# Greinke_Boost_Converter_Electromagnet_Sc.net
KiCad netlist of a schematic drawn in Altium Designer
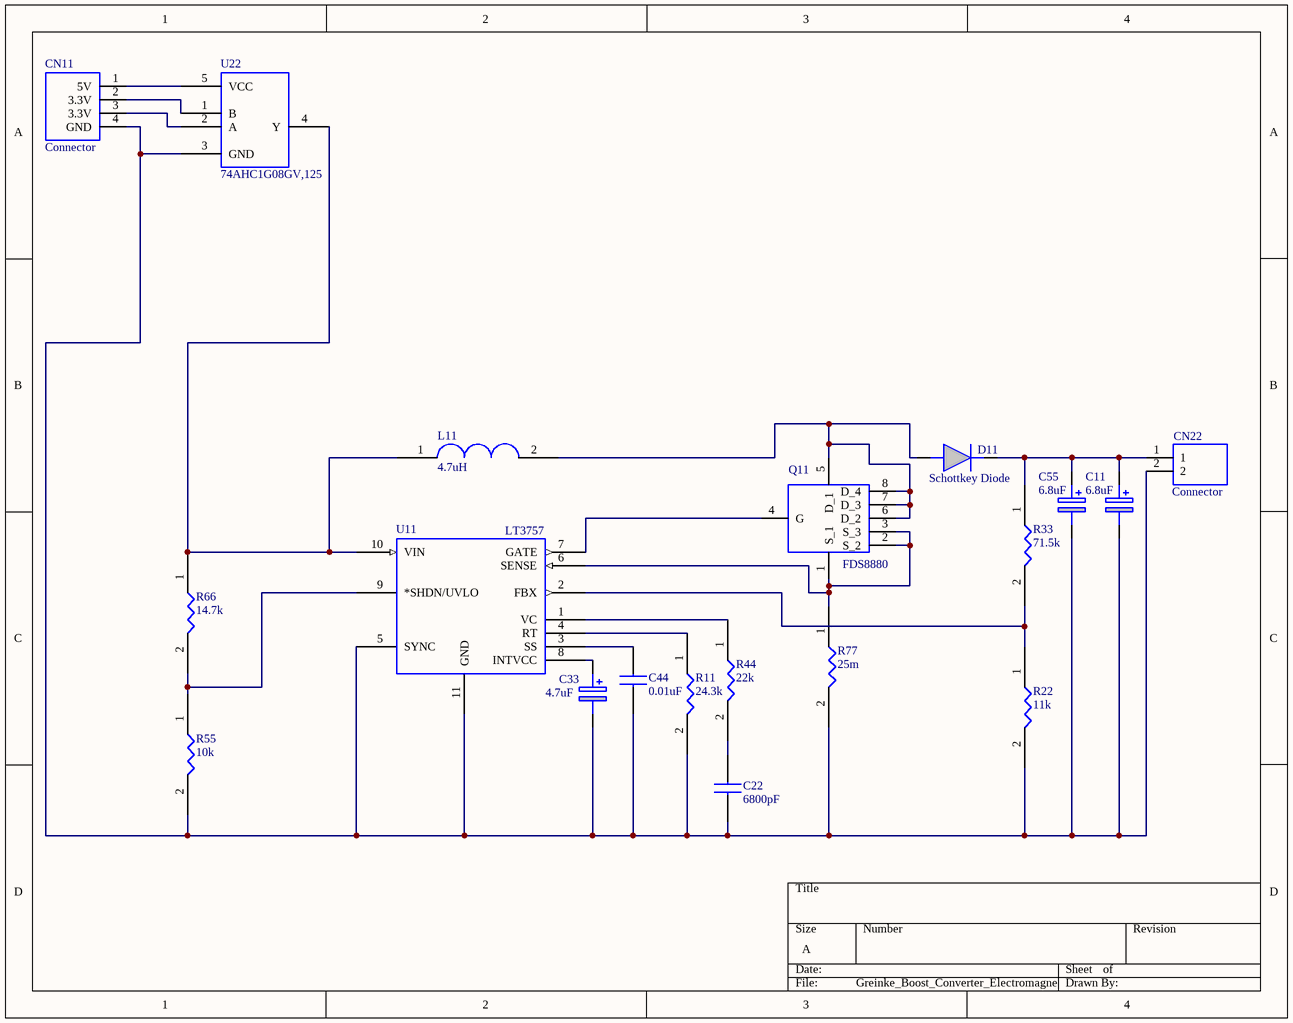
[diagram p0: Greinke_Boost_Converter_Electromagnet(Schematic).SchDoc]

(export (version "E")
  (design (tool "Eeschema 10.0.6"))
  (components
    (comp (ref "C11")
      (value "6.8uF")
      (footprint "6.8u Capacitor")
      (libsource (lib "Schlib1") (part "6.8u Capacitor"))
    )
    (comp (ref "C22")
      (value "6800pF")
      (footprint "6800p Capacitor")
      (libsource (lib "Schlib1") (part "6800p Capacitor"))
    )
    (comp (ref "C33")
      (value "4.7uF")
      (footprint "4.7u Capacitor")
      (libsource (lib "Schlib1") (part "4.7u Capacitor"))
    )
    (comp (ref "C44")
      (value "0.01uF")
      (footprint "0.01u Capacitor")
      (libsource (lib "Schlib1") (part "0.01u Capacitor_1"))
    )
    (comp (ref "C55")
      (value "6.8uF")
      (footprint "6.8u Capacitor")
      (libsource (lib "Schlib1") (part "6.8u Capacitor"))
    )
    (comp (ref "CN11")
      (value "Connector")
      (footprint "4 Terminal Block")
      (libsource (lib "Schlib1") (part "4 Terminal Block"))
    )
    (comp (ref "CN22")
      (value "Connector")
      (footprint "2 Terminal Blocks")
      (libsource (lib "Schlib1") (part "2 Terminal Blocks"))
    )
    (comp (ref "D11")
      (value "Schottkey Diode")
      (footprint "MBRS340")
      (libsource (lib "Schlib1") (part "MBRS340"))
    )
    (comp (ref "L11") (value "4.7uH") (footprint "744774047") (libsource (lib "Schlib1") (part "744774047")))
    (comp (ref "Q11") (value "FDS8880") (footprint "FDS8880") (libsource (lib "Schlib1") (part "FDS8880")))
    (comp (ref "R11")
      (value "24.3k")
      (footprint "24.3k Resistor")
      (libsource (lib "Schlib1") (part "24.3k Resistor"))
    )
    (comp (ref "R22")
      (value "11k")
      (footprint "11k Resistor")
      (libsource (lib "Schlib1") (part "11k Resistor"))
    )
    (comp (ref "R33")
      (value "71.5k")
      (footprint "71.5k Resistor")
      (libsource (lib "Schlib1") (part "71.5k Resistor"))
    )
    (comp (ref "R44")
      (value "22k")
      (footprint "22k Resistor")
      (libsource (lib "Schlib1") (part "22k Resistor"))
    )
    (comp (ref "R55")
      (value "10k")
      (footprint "10k Resistor")
      (libsource (lib "Schlib1") (part "10k Resistor"))
    )
    (comp (ref "R66")
      (value "14.7k")
      (footprint "14.7k Resistor")
      (libsource (lib "Schlib1") (part "14.7k Resistor"))
    )
    (comp (ref "R77")
      (value "25m")
      (footprint "25m Resistor")
      (libsource (lib "Schlib1") (part "25m Resistor"))
    )
    (comp (ref "U11") (value "LT3757") (footprint "LT3757") (libsource (lib "Schlib1") (part "LT3757")))
    (comp (ref "U22")
      (value "74AHC1G08GV,125")
      (footprint "74AHC1G08GV,125")
      (libsource (lib "Schlib1") (part "74AHC1G08GV,125"))
    )
  )
  (nets
    (net (code "1") (name "Net-(C11-+)") (class "Default")
      (node (ref "C11") (pin "1") (pinfunction "+_1") (pintype "passive"))
      (node (ref "C55") (pin "1") (pinfunction "+_1") (pintype "passive"))
      (node (ref "CN22") (pin "1") (pinfunction "1_1") (pintype "passive"))
      (node (ref "D11") (pin "1") (pinfunction "K_1") (pintype "passive"))
      (node (ref "R33") (pin "1") (pintype "passive"))
    )
    (net (code "2") (name "Net-(C11--)") (class "Default")
      (node (ref "C11") (pin "2") (pinfunction "-_2") (pintype "passive"))
      (node (ref "C22") (pin "2") (pinfunction "2_2") (pintype "passive"))
      (node (ref "C33") (pin "2") (pinfunction "-_2") (pintype "passive"))
      (node (ref "C44") (pin "1") (pinfunction "1_1") (pintype "passive"))
      (node (ref "C55") (pin "2") (pinfunction "-_2") (pintype "passive"))
      (node (ref "CN11") (pin "4") (pinfunction "GND_4") (pintype "passive"))
      (node (ref "CN22") (pin "2") (pinfunction "2_2") (pintype "passive"))
      (node (ref "R11") (pin "2") (pintype "passive"))
      (node (ref "R22") (pin "2") (pintype "passive"))
      (node (ref "R55") (pin "2") (pintype "passive"))
      (node (ref "R77") (pin "2") (pintype "passive"))
      (node (ref "U11") (pin "11") (pinfunction "GND_11") (pintype "passive"))
      (node (ref "U11") (pin "5") (pinfunction "SYNC_5") (pintype "passive"))
      (node (ref "U22") (pin "3") (pinfunction "GND_3") (pintype "passive"))
    )
    (net (code "3") (name "Net-(C22-Pad1)") (class "Default")
      (node (ref "C22") (pin "1") (pinfunction "1_1") (pintype "passive"))
      (node (ref "R44") (pin "2") (pintype "passive"))
    )
    (net (code "4") (name "Net-(C33-+)") (class "Default")
      (node (ref "C33") (pin "1") (pinfunction "+_1") (pintype "passive"))
      (node (ref "U11") (pin "8") (pinfunction "INTVCC_8") (pintype "passive"))
    )
    (net (code "5") (name "Net-(CN11-5V)") (class "Default")
      (node (ref "CN11") (pin "1") (pinfunction "5V_1") (pintype "passive"))
      (node (ref "U22") (pin "5") (pinfunction "VCC_5") (pintype "passive"))
    )
    (net (code "6") (name "Net-(D11-A)") (class "Default")
      (node (ref "D11") (pin "2") (pinfunction "A_2") (pintype "passive"))
      (node (ref "L11") (pin "2") (pintype "passive"))
      (node (ref "Q11") (pin "5") (pinfunction "D_1_5") (pintype "passive"))
      (node (ref "Q11") (pin "6") (pinfunction "D_2_6") (pintype "passive"))
      (node (ref "Q11") (pin "7") (pinfunction "D_3_7") (pintype "passive"))
      (node (ref "Q11") (pin "8") (pinfunction "D_4_8") (pintype "passive"))
    )
    (net (code "7") (name "Net-(Q11-G)") (class "Default")
      (node (ref "Q11") (pin "4") (pinfunction "G_4") (pintype "passive"))
      (node (ref "U11") (pin "7") (pinfunction "GATE_7") (pintype "output"))
    )
    (net (code "8") (name "Net-(Q11-S_1)") (class "Default")
      (node (ref "Q11") (pin "1") (pinfunction "S_1_1") (pintype "passive"))
      (node (ref "Q11") (pin "2") (pinfunction "S_2_2") (pintype "passive"))
      (node (ref "Q11") (pin "3") (pinfunction "S_3_3") (pintype "passive"))
      (node (ref "R77") (pin "1") (pintype "passive"))
      (node (ref "U11") (pin "6") (pinfunction "SENSE_6") (pintype "input"))
    )
    (net (code "9") (name "Net-(U11-*SHDN{slash}UVLO)") (class "Default")
      (node (ref "R55") (pin "1") (pintype "passive"))
      (node (ref "R66") (pin "2") (pintype "passive"))
      (node (ref "U11") (pin "9") (pinfunction "*SHDN/UVLO_9") (pintype "passive"))
    )
    (net (code "10") (name "Net-(U11-FBX)") (class "Default")
      (node (ref "R22") (pin "1") (pintype "passive"))
      (node (ref "R33") (pin "2") (pintype "passive"))
      (node (ref "U11") (pin "2") (pinfunction "FBX_2") (pintype "output"))
    )
    (net (code "11") (name "Net-(U11-RT)") (class "Default")
      (node (ref "R11") (pin "1") (pintype "passive"))
      (node (ref "U11") (pin "4") (pinfunction "RT_4") (pintype "passive"))
    )
    (net (code "12") (name "Net-(U11-SS)") (class "Default")
      (node (ref "C44") (pin "2") (pinfunction "2_2") (pintype "passive"))
      (node (ref "U11") (pin "3") (pinfunction "SS_3") (pintype "passive"))
    )
    (net (code "13") (name "Net-(U11-VC)") (class "Default")
      (node (ref "R44") (pin "1") (pintype "passive"))
      (node (ref "U11") (pin "1") (pinfunction "VC_1") (pintype "passive"))
    )
    (net (code "14") (name "Net-(U11-VIN)") (class "Default")
      (node (ref "L11") (pin "1") (pintype "passive"))
      (node (ref "R66") (pin "1") (pintype "passive"))
      (node (ref "U11") (pin "10") (pinfunction "VIN_10") (pintype "input"))
      (node (ref "U22") (pin "4") (pinfunction "Y_4") (pintype "passive"))
    )
    (net (code "15") (name "Net-(U22-A)") (class "Default")
      (node (ref "CN11") (pin "3") (pinfunction "3.3V_3") (pintype "passive"))
      (node (ref "U22") (pin "2") (pinfunction "A_2") (pintype "passive"))
    )
    (net (code "16") (name "Net-(U22-B)") (class "Default")
      (node (ref "CN11") (pin "2") (pinfunction "3.3V_2") (pintype "passive"))
      (node (ref "U22") (pin "1") (pinfunction "B_1") (pintype "passive"))
    )
  )
)
